# 2_cyber60-mx-matrix.net
KiCad netlist of a schematic drawn in Altium Designer
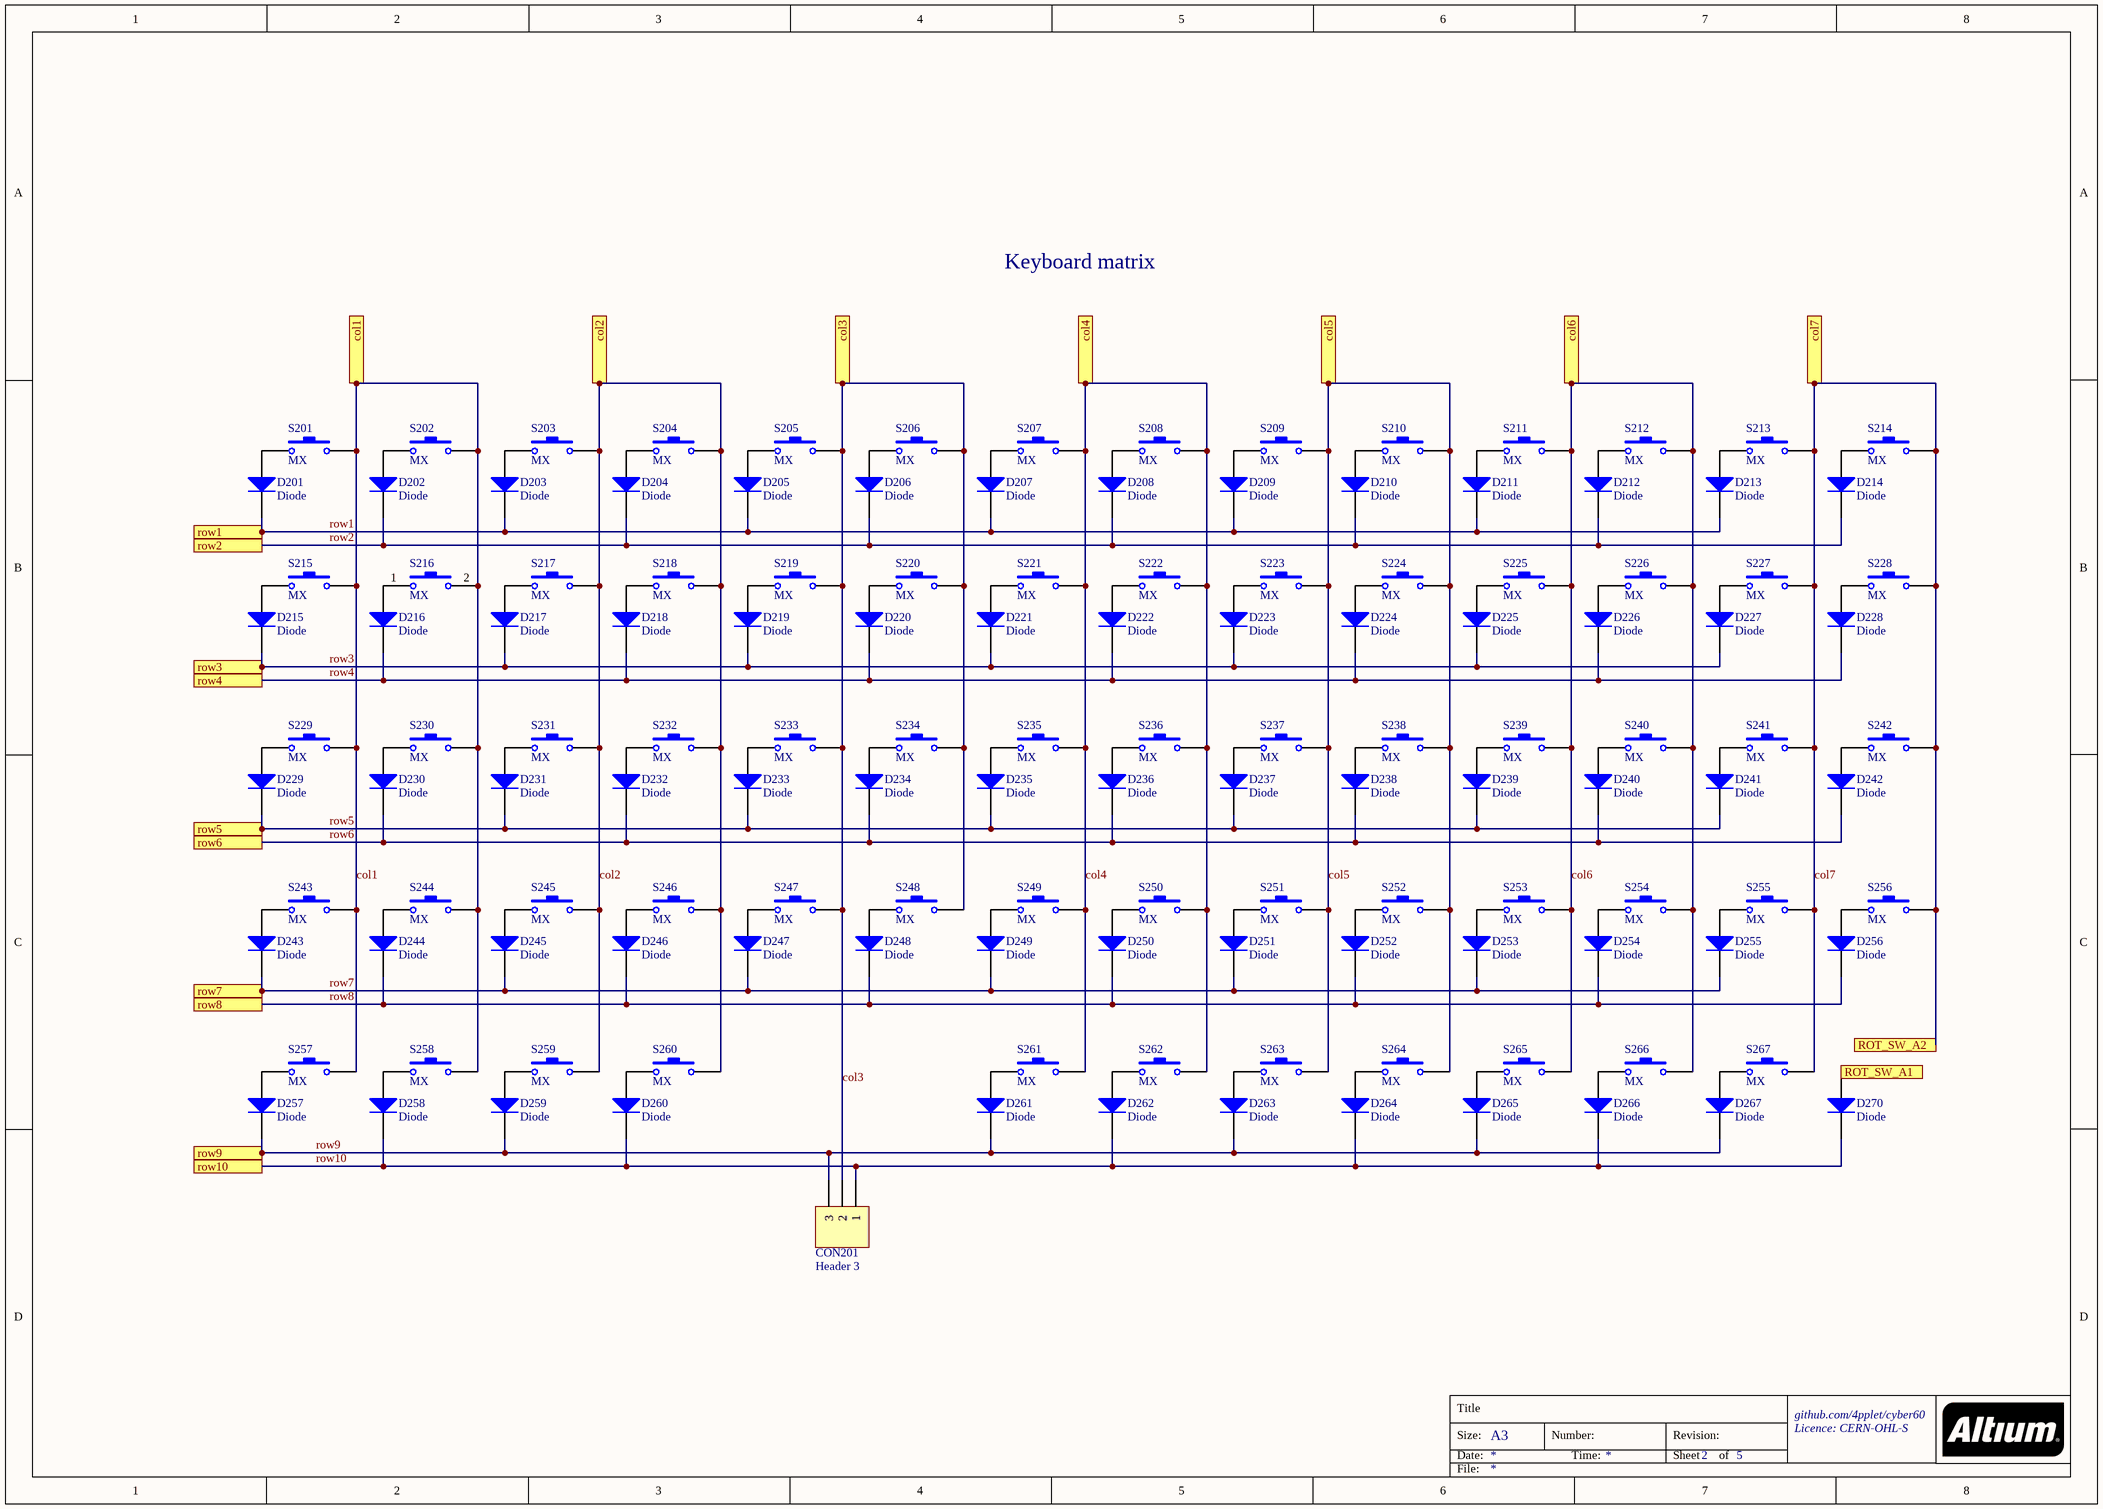
[diagram p0: 2_cyber60-mx-matrix.SchDoc]

(export (version "E")
  (design (tool "Eeschema 10.0.6"))
  (components
    (comp (ref "CON201")
      (value "Header 3")
      (footprint "HDR1X3")
      (description "Header, 3-Pin")
      (libsource (lib "Miscellaneous Connectors") (part "Header 3"))
    )
    (comp (ref "D201")
      (value "Diode")
      (footprint "SOD-123")
      (description "Default Diode")
      (fields (field (name "LCSC PART #") "C81598") (field (name "MRF.PART") "1N4148W"))
      (libsource (lib "Miscellaneous Devices") (part "Diode"))
    )
    (comp (ref "D202")
      (value "Diode")
      (footprint "SOD-123")
      (description "Default Diode")
      (fields (field (name "LCSC PART #") "C81598") (field (name "MRF.PART") "1N4148W"))
      (libsource (lib "Miscellaneous Devices") (part "Diode"))
    )
    (comp (ref "D203")
      (value "Diode")
      (footprint "SOD-123")
      (description "Default Diode")
      (fields (field (name "LCSC PART #") "C81598") (field (name "MRF.PART") "1N4148W"))
      (libsource (lib "Miscellaneous Devices") (part "Diode"))
    )
    (comp (ref "D204")
      (value "Diode")
      (footprint "SOD-123")
      (description "Default Diode")
      (fields (field (name "LCSC PART #") "C81598") (field (name "MRF.PART") "1N4148W"))
      (libsource (lib "Miscellaneous Devices") (part "Diode"))
    )
    (comp (ref "D205")
      (value "Diode")
      (footprint "SOD-123")
      (description "Default Diode")
      (fields (field (name "LCSC PART #") "C81598") (field (name "MRF.PART") "1N4148W"))
      (libsource (lib "Miscellaneous Devices") (part "Diode"))
    )
    (comp (ref "D206")
      (value "Diode")
      (footprint "SOD-123")
      (description "Default Diode")
      (fields (field (name "LCSC PART #") "C81598") (field (name "MRF.PART") "1N4148W"))
      (libsource (lib "Miscellaneous Devices") (part "Diode"))
    )
    (comp (ref "D207")
      (value "Diode")
      (footprint "SOD-123")
      (description "Default Diode")
      (fields (field (name "LCSC PART #") "C81598") (field (name "MRF.PART") "1N4148W"))
      (libsource (lib "Miscellaneous Devices") (part "Diode"))
    )
    (comp (ref "D208")
      (value "Diode")
      (footprint "SOD-123")
      (description "Default Diode")
      (fields (field (name "LCSC PART #") "C81598") (field (name "MRF.PART") "1N4148W"))
      (libsource (lib "Miscellaneous Devices") (part "Diode"))
    )
    (comp (ref "D209")
      (value "Diode")
      (footprint "SOD-123")
      (description "Default Diode")
      (fields (field (name "LCSC PART #") "C81598") (field (name "MRF.PART") "1N4148W"))
      (libsource (lib "Miscellaneous Devices") (part "Diode"))
    )
    (comp (ref "D210")
      (value "Diode")
      (footprint "SOD-123")
      (description "Default Diode")
      (fields (field (name "LCSC PART #") "C81598") (field (name "MRF.PART") "1N4148W"))
      (libsource (lib "Miscellaneous Devices") (part "Diode"))
    )
    (comp (ref "D211")
      (value "Diode")
      (footprint "SOD-123")
      (description "Default Diode")
      (fields (field (name "LCSC PART #") "C81598") (field (name "MRF.PART") "1N4148W"))
      (libsource (lib "Miscellaneous Devices") (part "Diode"))
    )
    (comp (ref "D212")
      (value "Diode")
      (footprint "SOD-123")
      (description "Default Diode")
      (fields (field (name "LCSC PART #") "C81598") (field (name "MRF.PART") "1N4148W"))
      (libsource (lib "Miscellaneous Devices") (part "Diode"))
    )
    (comp (ref "D213")
      (value "Diode")
      (footprint "SOD-123")
      (description "Default Diode")
      (fields (field (name "LCSC PART #") "C81598") (field (name "MRF.PART") "1N4148W"))
      (libsource (lib "Miscellaneous Devices") (part "Diode"))
    )
    (comp (ref "D214")
      (value "Diode")
      (footprint "SOD-123")
      (description "Default Diode")
      (fields (field (name "LCSC PART #") "C81598") (field (name "MRF.PART") "1N4148W"))
      (libsource (lib "Miscellaneous Devices") (part "Diode"))
    )
    (comp (ref "D215")
      (value "Diode")
      (footprint "SOD-123")
      (description "Default Diode")
      (fields (field (name "LCSC PART #") "C81598") (field (name "MRF.PART") "1N4148W"))
      (libsource (lib "Miscellaneous Devices") (part "Diode"))
    )
    (comp (ref "D216")
      (value "Diode")
      (footprint "SOD-123")
      (description "Default Diode")
      (fields (field (name "LCSC PART #") "C81598") (field (name "MRF.PART") "1N4148W"))
      (libsource (lib "Miscellaneous Devices") (part "Diode"))
    )
    (comp (ref "D217")
      (value "Diode")
      (footprint "SOD-123")
      (description "Default Diode")
      (fields (field (name "LCSC PART #") "C81598") (field (name "MRF.PART") "1N4148W"))
      (libsource (lib "Miscellaneous Devices") (part "Diode"))
    )
    (comp (ref "D218")
      (value "Diode")
      (footprint "SOD-123")
      (description "Default Diode")
      (fields (field (name "LCSC PART #") "C81598") (field (name "MRF.PART") "1N4148W"))
      (libsource (lib "Miscellaneous Devices") (part "Diode"))
    )
    (comp (ref "D219")
      (value "Diode")
      (footprint "SOD-123")
      (description "Default Diode")
      (fields (field (name "LCSC PART #") "C81598") (field (name "MRF.PART") "1N4148W"))
      (libsource (lib "Miscellaneous Devices") (part "Diode"))
    )
    (comp (ref "D220")
      (value "Diode")
      (footprint "SOD-123")
      (description "Default Diode")
      (fields (field (name "LCSC PART #") "C81598") (field (name "MRF.PART") "1N4148W"))
      (libsource (lib "Miscellaneous Devices") (part "Diode"))
    )
    (comp (ref "D221")
      (value "Diode")
      (footprint "SOD-123")
      (description "Default Diode")
      (fields (field (name "LCSC PART #") "C81598") (field (name "MRF.PART") "1N4148W"))
      (libsource (lib "Miscellaneous Devices") (part "Diode"))
    )
    (comp (ref "D222")
      (value "Diode")
      (footprint "SOD-123")
      (description "Default Diode")
      (fields (field (name "LCSC PART #") "C81598") (field (name "MRF.PART") "1N4148W"))
      (libsource (lib "Miscellaneous Devices") (part "Diode"))
    )
    (comp (ref "D223")
      (value "Diode")
      (footprint "SOD-123")
      (description "Default Diode")
      (fields (field (name "LCSC PART #") "C81598") (field (name "MRF.PART") "1N4148W"))
      (libsource (lib "Miscellaneous Devices") (part "Diode"))
    )
    (comp (ref "D224")
      (value "Diode")
      (footprint "SOD-123")
      (description "Default Diode")
      (fields (field (name "LCSC PART #") "C81598") (field (name "MRF.PART") "1N4148W"))
      (libsource (lib "Miscellaneous Devices") (part "Diode"))
    )
    (comp (ref "D225")
      (value "Diode")
      (footprint "SOD-123")
      (description "Default Diode")
      (fields (field (name "LCSC PART #") "C81598") (field (name "MRF.PART") "1N4148W"))
      (libsource (lib "Miscellaneous Devices") (part "Diode"))
    )
    (comp (ref "D226")
      (value "Diode")
      (footprint "SOD-123")
      (description "Default Diode")
      (fields (field (name "LCSC PART #") "C81598") (field (name "MRF.PART") "1N4148W"))
      (libsource (lib "Miscellaneous Devices") (part "Diode"))
    )
    (comp (ref "D227")
      (value "Diode")
      (footprint "SOD-123")
      (description "Default Diode")
      (fields (field (name "LCSC PART #") "C81598") (field (name "MRF.PART") "1N4148W"))
      (libsource (lib "Miscellaneous Devices") (part "Diode"))
    )
    (comp (ref "D228")
      (value "Diode")
      (footprint "SOD-123")
      (description "Default Diode")
      (fields (field (name "LCSC PART #") "C81598") (field (name "MRF.PART") "1N4148W"))
      (libsource (lib "Miscellaneous Devices") (part "Diode"))
    )
    (comp (ref "D229")
      (value "Diode")
      (footprint "SOD-123")
      (description "Default Diode")
      (fields (field (name "LCSC PART #") "C81598") (field (name "MRF.PART") "1N4148W"))
      (libsource (lib "Miscellaneous Devices") (part "Diode"))
    )
    (comp (ref "D230")
      (value "Diode")
      (footprint "SOD-123")
      (description "Default Diode")
      (fields (field (name "LCSC PART #") "C81598") (field (name "MRF.PART") "1N4148W"))
      (libsource (lib "Miscellaneous Devices") (part "Diode"))
    )
    (comp (ref "D231")
      (value "Diode")
      (footprint "SOD-123")
      (description "Default Diode")
      (fields (field (name "LCSC PART #") "C81598") (field (name "MRF.PART") "1N4148W"))
      (libsource (lib "Miscellaneous Devices") (part "Diode"))
    )
    (comp (ref "D232")
      (value "Diode")
      (footprint "SOD-123")
      (description "Default Diode")
      (fields (field (name "LCSC PART #") "C81598") (field (name "MRF.PART") "1N4148W"))
      (libsource (lib "Miscellaneous Devices") (part "Diode"))
    )
    (comp (ref "D233")
      (value "Diode")
      (footprint "SOD-123")
      (description "Default Diode")
      (fields (field (name "LCSC PART #") "C81598") (field (name "MRF.PART") "1N4148W"))
      (libsource (lib "Miscellaneous Devices") (part "Diode"))
    )
    (comp (ref "D234")
      (value "Diode")
      (footprint "SOD-123")
      (description "Default Diode")
      (fields (field (name "LCSC PART #") "C81598") (field (name "MRF.PART") "1N4148W"))
      (libsource (lib "Miscellaneous Devices") (part "Diode"))
    )
    (comp (ref "D235")
      (value "Diode")
      (footprint "SOD-123")
      (description "Default Diode")
      (fields (field (name "LCSC PART #") "C81598") (field (name "MRF.PART") "1N4148W"))
      (libsource (lib "Miscellaneous Devices") (part "Diode"))
    )
    (comp (ref "D236")
      (value "Diode")
      (footprint "SOD-123")
      (description "Default Diode")
      (fields (field (name "LCSC PART #") "C81598") (field (name "MRF.PART") "1N4148W"))
      (libsource (lib "Miscellaneous Devices") (part "Diode"))
    )
    (comp (ref "D237")
      (value "Diode")
      (footprint "SOD-123")
      (description "Default Diode")
      (fields (field (name "LCSC PART #") "C81598") (field (name "MRF.PART") "1N4148W"))
      (libsource (lib "Miscellaneous Devices") (part "Diode"))
    )
    (comp (ref "D238")
      (value "Diode")
      (footprint "SOD-123")
      (description "Default Diode")
      (fields (field (name "LCSC PART #") "C81598") (field (name "MRF.PART") "1N4148W"))
      (libsource (lib "Miscellaneous Devices") (part "Diode"))
    )
    (comp (ref "D239")
      (value "Diode")
      (footprint "SOD-123")
      (description "Default Diode")
      (fields (field (name "LCSC PART #") "C81598") (field (name "MRF.PART") "1N4148W"))
      (libsource (lib "Miscellaneous Devices") (part "Diode"))
    )
    (comp (ref "D240")
      (value "Diode")
      (footprint "SOD-123")
      (description "Default Diode")
      (fields (field (name "LCSC PART #") "C81598") (field (name "MRF.PART") "1N4148W"))
      (libsource (lib "Miscellaneous Devices") (part "Diode"))
    )
    (comp (ref "D241")
      (value "Diode")
      (footprint "SOD-123")
      (description "Default Diode")
      (fields (field (name "LCSC PART #") "C81598") (field (name "MRF.PART") "1N4148W"))
      (libsource (lib "Miscellaneous Devices") (part "Diode"))
    )
    (comp (ref "D242")
      (value "Diode")
      (footprint "SOD-123")
      (description "Default Diode")
      (fields (field (name "LCSC PART #") "C81598") (field (name "MRF.PART") "1N4148W"))
      (libsource (lib "Miscellaneous Devices") (part "Diode"))
    )
    (comp (ref "D243")
      (value "Diode")
      (footprint "SOD-123")
      (description "Default Diode")
      (fields (field (name "LCSC PART #") "C81598") (field (name "MRF.PART") "1N4148W"))
      (libsource (lib "Miscellaneous Devices") (part "Diode"))
    )
    (comp (ref "D244")
      (value "Diode")
      (footprint "SOD-123")
      (description "Default Diode")
      (fields (field (name "LCSC PART #") "C81598") (field (name "MRF.PART") "1N4148W"))
      (libsource (lib "Miscellaneous Devices") (part "Diode"))
    )
    (comp (ref "D245")
      (value "Diode")
      (footprint "SOD-123")
      (description "Default Diode")
      (fields (field (name "LCSC PART #") "C81598") (field (name "MRF.PART") "1N4148W"))
      (libsource (lib "Miscellaneous Devices") (part "Diode"))
    )
    (comp (ref "D246")
      (value "Diode")
      (footprint "SOD-123")
      (description "Default Diode")
      (fields (field (name "LCSC PART #") "C81598") (field (name "MRF.PART") "1N4148W"))
      (libsource (lib "Miscellaneous Devices") (part "Diode"))
    )
    (comp (ref "D247")
      (value "Diode")
      (footprint "SOD-123")
      (description "Default Diode")
      (fields (field (name "LCSC PART #") "C81598") (field (name "MRF.PART") "1N4148W"))
      (libsource (lib "Miscellaneous Devices") (part "Diode"))
    )
    (comp (ref "D248")
      (value "Diode")
      (footprint "SOD-123")
      (description "Default Diode")
      (fields (field (name "LCSC PART #") "C81598") (field (name "MRF.PART") "1N4148W"))
      (libsource (lib "Miscellaneous Devices") (part "Diode"))
    )
    (comp (ref "D249")
      (value "Diode")
      (footprint "SOD-123")
      (description "Default Diode")
      (fields (field (name "LCSC PART #") "C81598") (field (name "MRF.PART") "1N4148W"))
      (libsource (lib "Miscellaneous Devices") (part "Diode"))
    )
    (comp (ref "D250")
      (value "Diode")
      (footprint "SOD-123")
      (description "Default Diode")
      (fields (field (name "LCSC PART #") "C81598") (field (name "MRF.PART") "1N4148W"))
      (libsource (lib "Miscellaneous Devices") (part "Diode"))
    )
    (comp (ref "D251")
      (value "Diode")
      (footprint "SOD-123")
      (description "Default Diode")
      (fields (field (name "LCSC PART #") "C81598") (field (name "MRF.PART") "1N4148W"))
      (libsource (lib "Miscellaneous Devices") (part "Diode"))
    )
    (comp (ref "D252")
      (value "Diode")
      (footprint "SOD-123")
      (description "Default Diode")
      (fields (field (name "LCSC PART #") "C81598") (field (name "MRF.PART") "1N4148W"))
      (libsource (lib "Miscellaneous Devices") (part "Diode"))
    )
    (comp (ref "D253")
      (value "Diode")
      (footprint "SOD-123")
      (description "Default Diode")
      (fields (field (name "LCSC PART #") "C81598") (field (name "MRF.PART") "1N4148W"))
      (libsource (lib "Miscellaneous Devices") (part "Diode"))
    )
    (comp (ref "D254")
      (value "Diode")
      (footprint "SOD-123")
      (description "Default Diode")
      (fields (field (name "LCSC PART #") "C81598") (field (name "MRF.PART") "1N4148W"))
      (libsource (lib "Miscellaneous Devices") (part "Diode"))
    )
    (comp (ref "D255")
      (value "Diode")
      (footprint "SOD-123")
      (description "Default Diode")
      (fields (field (name "LCSC PART #") "C81598") (field (name "MRF.PART") "1N4148W"))
      (libsource (lib "Miscellaneous Devices") (part "Diode"))
    )
    (comp (ref "D256")
      (value "Diode")
      (footprint "SOD-123")
      (description "Default Diode")
      (fields (field (name "LCSC PART #") "C81598") (field (name "MRF.PART") "1N4148W"))
      (libsource (lib "Miscellaneous Devices") (part "Diode"))
    )
    (comp (ref "D257")
      (value "Diode")
      (footprint "SOD-123")
      (description "Default Diode")
      (fields (field (name "LCSC PART #") "C81598") (field (name "MRF.PART") "1N4148W"))
      (libsource (lib "Miscellaneous Devices") (part "Diode"))
    )
    (comp (ref "D258")
      (value "Diode")
      (footprint "SOD-123")
      (description "Default Diode")
      (fields (field (name "LCSC PART #") "C81598") (field (name "MRF.PART") "1N4148W"))
      (libsource (lib "Miscellaneous Devices") (part "Diode"))
    )
    (comp (ref "D259")
      (value "Diode")
      (footprint "SOD-123")
      (description "Default Diode")
      (fields (field (name "LCSC PART #") "C81598") (field (name "MRF.PART") "1N4148W"))
      (libsource (lib "Miscellaneous Devices") (part "Diode"))
    )
    (comp (ref "D260")
      (value "Diode")
      (footprint "SOD-123")
      (description "Default Diode")
      (fields (field (name "LCSC PART #") "C81598") (field (name "MRF.PART") "1N4148W"))
      (libsource (lib "Miscellaneous Devices") (part "Diode"))
    )
    (comp (ref "D261")
      (value "Diode")
      (footprint "SOD-123")
      (description "Default Diode")
      (fields (field (name "LCSC PART #") "C81598") (field (name "MRF.PART") "1N4148W"))
      (libsource (lib "Miscellaneous Devices") (part "Diode"))
    )
    (comp (ref "D262")
      (value "Diode")
      (footprint "SOD-123")
      (description "Default Diode")
      (fields (field (name "LCSC PART #") "C81598") (field (name "MRF.PART") "1N4148W"))
      (libsource (lib "Miscellaneous Devices") (part "Diode"))
    )
    (comp (ref "D263")
      (value "Diode")
      (footprint "SOD-123")
      (description "Default Diode")
      (fields (field (name "LCSC PART #") "C81598") (field (name "MRF.PART") "1N4148W"))
      (libsource (lib "Miscellaneous Devices") (part "Diode"))
    )
    (comp (ref "D264")
      (value "Diode")
      (footprint "SOD-123")
      (description "Default Diode")
      (fields (field (name "LCSC PART #") "C81598") (field (name "MRF.PART") "1N4148W"))
      (libsource (lib "Miscellaneous Devices") (part "Diode"))
    )
    (comp (ref "D265")
      (value "Diode")
      (footprint "SOD-123")
      (description "Default Diode")
      (fields (field (name "LCSC PART #") "C81598") (field (name "MRF.PART") "1N4148W"))
      (libsource (lib "Miscellaneous Devices") (part "Diode"))
    )
    (comp (ref "D266")
      (value "Diode")
      (footprint "SOD-123")
      (description "Default Diode")
      (fields (field (name "LCSC PART #") "C81598") (field (name "MRF.PART") "1N4148W"))
      (libsource (lib "Miscellaneous Devices") (part "Diode"))
    )
    (comp (ref "D267")
      (value "Diode")
      (footprint "SOD-123")
      (description "Default Diode")
      (fields (field (name "LCSC PART #") "C81598") (field (name "MRF.PART") "1N4148W"))
      (libsource (lib "Miscellaneous Devices") (part "Diode"))
    )
    (comp (ref "D270")
      (value "Diode")
      (footprint "SOD-123")
      (description "Default Diode")
      (fields (field (name "LCSC PART #") "C81598") (field (name "MRF.PART") "1N4148W"))
      (libsource (lib "Miscellaneous Devices") (part "Diode"))
    )
    (comp (ref "S201")
      (value "MX")
      (footprint "MX-switch - switched pol")
      (description "Switch")
      (libsource (lib "Miscellaneous Devices") (part "SW-PB"))
    )
    (comp (ref "S202")
      (value "MX")
      (footprint "MX-switch - switched pol - connector")
      (description "Switch")
      (libsource (lib "Miscellaneous Devices") (part "SW-PB"))
    )
    (comp (ref "S203")
      (value "MX")
      (footprint "MX-switch - switched pol")
      (description "Switch")
      (libsource (lib "Miscellaneous Devices") (part "SW-PB"))
    )
    (comp (ref "S204")
      (value "MX")
      (footprint "MX-switch")
      (description "Switch")
      (libsource (lib "Miscellaneous Devices") (part "SW-PB"))
    )
    (comp (ref "S205")
      (value "MX")
      (footprint "MX-switch - switched pol")
      (description "Switch")
      (libsource (lib "Miscellaneous Devices") (part "SW-PB"))
    )
    (comp (ref "S206")
      (value "MX")
      (footprint "MX-switch - switched pol")
      (description "Switch")
      (libsource (lib "Miscellaneous Devices") (part "SW-PB"))
    )
    (comp (ref "S207")
      (value "MX")
      (footprint "MX-switch - switched pol")
      (description "Switch")
      (libsource (lib "Miscellaneous Devices") (part "SW-PB"))
    )
    (comp (ref "S208")
      (value "MX")
      (footprint "MX-switch - switched pol")
      (description "Switch")
      (libsource (lib "Miscellaneous Devices") (part "SW-PB"))
    )
    (comp (ref "S209")
      (value "MX")
      (footprint "MX-switch - switched pol")
      (description "Switch")
      (libsource (lib "Miscellaneous Devices") (part "SW-PB"))
    )
    (comp (ref "S210")
      (value "MX")
      (footprint "MX-switch - switched pol")
      (description "Switch")
      (libsource (lib "Miscellaneous Devices") (part "SW-PB"))
    )
    (comp (ref "S211")
      (value "MX")
      (footprint "MX-switch - switched pol")
      (description "Switch")
      (libsource (lib "Miscellaneous Devices") (part "SW-PB"))
    )
    (comp (ref "S212")
      (value "MX")
      (footprint "MX-switch - switched pol")
      (description "Switch")
      (libsource (lib "Miscellaneous Devices") (part "SW-PB"))
    )
    (comp (ref "S213")
      (value "MX")
      (footprint "MX-switch - switched pol")
      (description "Switch")
      (libsource (lib "Miscellaneous Devices") (part "SW-PB"))
    )
    (comp (ref "S214")
      (value "MX")
      (footprint "MX-switch - switched pol")
      (description "Switch")
      (libsource (lib "Miscellaneous Devices") (part "SW-PB"))
    )
    (comp (ref "S215")
      (value "MX")
      (footprint "MX-switch - 1.5U - switched pol")
      (description "TAB")
      (libsource (lib "Miscellaneous Devices") (part "SW-PB"))
    )
    (comp (ref "S216")
      (value "MX")
      (footprint "MX-switch - switched pol")
      (description "Switch")
      (libsource (lib "") (part "SW-PB_1"))
    )
    (comp (ref "S217")
      (value "MX")
      (footprint "MX-switch - switched pol")
      (description "Switch")
      (libsource (lib "Miscellaneous Devices") (part "SW-PB"))
    )
    (comp (ref "S218")
      (value "MX")
      (footprint "MX-switch - switched pol")
      (description "Switch")
      (libsource (lib "Miscellaneous Devices") (part "SW-PB"))
    )
    (comp (ref "S219")
      (value "MX")
      (footprint "MX-switch - switched pol")
      (description "Switch")
      (libsource (lib "Miscellaneous Devices") (part "SW-PB"))
    )
    (comp (ref "S220")
      (value "MX")
      (footprint "MX-switch")
      (description "Switch")
      (libsource (lib "Miscellaneous Devices") (part "SW-PB"))
    )
    (comp (ref "S221")
      (value "MX")
      (footprint "MX-switch - switched pol")
      (description "Switch")
      (libsource (lib "Miscellaneous Devices") (part "SW-PB"))
    )
    (comp (ref "S222")
      (value "MX")
      (footprint "MX-switch - switched pol")
      (description "Switch")
      (libsource (lib "Miscellaneous Devices") (part "SW-PB"))
    )
    (comp (ref "S223")
      (value "MX")
      (footprint "MX-switch - switched pol")
      (description "Switch")
      (libsource (lib "Miscellaneous Devices") (part "SW-PB"))
    )
    (comp (ref "S224")
      (value "MX")
      (footprint "MX-switch - switched pol")
      (description "Switch")
      (libsource (lib "Miscellaneous Devices") (part "SW-PB"))
    )
    (comp (ref "S225")
      (value "MX")
      (footprint "MX-switch - switched pol")
      (description "Switch")
      (libsource (lib "Miscellaneous Devices") (part "SW-PB"))
    )
    (comp (ref "S226")
      (value "MX")
      (footprint "MX-switch")
      (description "Switch")
      (libsource (lib "Miscellaneous Devices") (part "SW-PB"))
    )
    (comp (ref "S227")
      (value "MX")
      (footprint "MX-switch")
      (description "Switch")
      (libsource (lib "Miscellaneous Devices") (part "SW-PB"))
    )
    (comp (ref "S228")
      (value "MX")
      (footprint "MX-switch - backspace")
      (description "Switch")
      (libsource (lib "Miscellaneous Devices") (part "SW-PB"))
    )
    (comp (ref "S229")
      (value "MX")
      (footprint "MX-switch - CAPS")
      (description "Switch")
      (libsource (lib "Miscellaneous Devices") (part "SW-PB"))
    )
    (comp (ref "S230")
      (value "MX")
      (footprint "MX-switch - switched pol")
      (description "Switch")
      (libsource (lib "Miscellaneous Devices") (part "SW-PB"))
    )
    (comp (ref "S231")
      (value "MX")
      (footprint "MX-switch - switched pol")
      (description "Switch")
      (libsource (lib "Miscellaneous Devices") (part "SW-PB"))
    )
    (comp (ref "S232")
      (value "MX")
      (footprint "MX-switch - switched pol")
      (description "Switch")
      (libsource (lib "Miscellaneous Devices") (part "SW-PB"))
    )
    (comp (ref "S233")
      (value "MX")
      (footprint "MX-switch - switched pol")
      (description "Switch")
      (libsource (lib "Miscellaneous Devices") (part "SW-PB"))
    )
    (comp (ref "S234")
      (value "MX")
      (footprint "MX-switch")
      (description "Switch")
      (libsource (lib "Miscellaneous Devices") (part "SW-PB"))
    )
    (comp (ref "S235")
      (value "MX")
      (footprint "MX-switch - switched pol")
      (description "Switch")
      (libsource (lib "Miscellaneous Devices") (part "SW-PB"))
    )
    (comp (ref "S236")
      (value "MX")
      (footprint "MX-switch - switched pol")
      (description "Switch")
      (libsource (lib "Miscellaneous Devices") (part "SW-PB"))
    )
    (comp (ref "S237")
      (value "MX")
      (footprint "MX-switch - switched pol")
      (description "Switch")
      (libsource (lib "Miscellaneous Devices") (part "SW-PB"))
    )
    (comp (ref "S238")
      (value "MX")
      (footprint "MX-switch - switched pol")
      (description "Switch")
      (libsource (lib "Miscellaneous Devices") (part "SW-PB"))
    )
    (comp (ref "S239")
      (value "MX")
      (footprint "MX-switch")
      (description "Switch")
      (libsource (lib "Miscellaneous Devices") (part "SW-PB"))
    )
    (comp (ref "S240")
      (value "MX")
      (footprint "MX-switch - switched pol")
      (description "Switch")
      (libsource (lib "Miscellaneous Devices") (part "SW-PB"))
    )
    (comp (ref "S241")
      (value "MX")
      (footprint "MX-switch")
      (description "Switch")
      (libsource (lib "Miscellaneous Devices") (part "SW-PB"))
    )
    (comp (ref "S242")
      (value "MX")
      (footprint "MX-switch - 1.5U")
      (description "Switch")
      (libsource (lib "Miscellaneous Devices") (part "SW-PB"))
    )
    (comp (ref "S243")
      (value "MX")
      (footprint "MX-switch - Left shift")
      (description "Switch")
      (libsource (lib "Miscellaneous Devices") (part "SW-PB"))
    )
    (comp (ref "S244")
      (value "MX")
      (footprint "MX-switch - switched pol")
      (description "Switch")
      (libsource (lib "Miscellaneous Devices") (part "SW-PB"))
    )
    (comp (ref "S245")
      (value "MX")
      (footprint "MX-switch - switched pol")
      (description "Switch")
      (libsource (lib "Miscellaneous Devices") (part "SW-PB"))
    )
    (comp (ref "S246")
      (value "MX")
      (footprint "MX-switch - switched pol")
      (description "Switch")
      (libsource (lib "Miscellaneous Devices") (part "SW-PB"))
    )
    (comp (ref "S247")
      (value "MX")
      (footprint "MX-switch - switched pol")
      (description "Switch")
      (libsource (lib "Miscellaneous Devices") (part "SW-PB"))
    )
    (comp (ref "S248")
      (value "MX")
      (footprint "MX-switch")
      (description "Switch")
      (libsource (lib "Miscellaneous Devices") (part "SW-PB"))
    )
    (comp (ref "S249")
      (value "MX")
      (footprint "MX-switch - switched pol")
      (description "Switch")
      (libsource (lib "Miscellaneous Devices") (part "SW-PB"))
    )
    (comp (ref "S250")
      (value "MX")
      (footprint "MX-switch - switched pol")
      (description "Switch")
      (libsource (lib "Miscellaneous Devices") (part "SW-PB"))
    )
    (comp (ref "S251")
      (value "MX")
      (footprint "MX-switch - switched pol")
      (description "Switch")
      (libsource (lib "Miscellaneous Devices") (part "SW-PB"))
    )
    (comp (ref "S252")
      (value "MX")
      (footprint "MX-switch - switched pol")
      (description "Switch")
      (libsource (lib "Miscellaneous Devices") (part "SW-PB"))
    )
    (comp (ref "S253")
      (value "MX")
      (footprint "MX-switch - switched pol")
      (description "Switch")
      (libsource (lib "Miscellaneous Devices") (part "SW-PB"))
    )
    (comp (ref "S254")
      (value "MX")
      (footprint "MX-switch - switched pol")
      (description "Switch")
      (libsource (lib "Miscellaneous Devices") (part "SW-PB"))
    )
    (comp (ref "S255")
      (value "MX")
      (footprint "MX-switch")
      (description "Switch")
      (libsource (lib "Miscellaneous Devices") (part "SW-PB"))
    )
    (comp (ref "S256")
      (value "MX")
      (footprint "MX-switch - Enter")
      (description "Switch")
      (libsource (lib "Miscellaneous Devices") (part "SW-PB"))
    )
    (comp (ref "S257")
      (value "MX")
      (footprint "MX-switch - 1.5u MOD-L")
      (description "Switch")
      (libsource (lib "Miscellaneous Devices") (part "SW-PB"))
    )
    (comp (ref "S258")
      (value "MX")
      (footprint "MX-switch - 1u MOD-L")
      (description "Switch")
      (libsource (lib "Miscellaneous Devices") (part "SW-PB"))
    )
    (comp (ref "S259")
      (value "MX")
      (footprint "MX-switch - 1.5u MOD-L")
      (description "Switch")
      (libsource (lib "Miscellaneous Devices") (part "SW-PB"))
    )
    (comp (ref "S260")
      (value "MX")
      (footprint "MX-switch - L split space_V2")
      (description "Switch")
      (libsource (lib "Miscellaneous Devices") (part "SW-PB"))
    )
    (comp (ref "S261")
      (value "MX")
      (footprint "MX-switch - Space_V3")
      (description "Switch")
      (libsource (lib "Miscellaneous Devices") (part "SW-PB"))
    )
    (comp (ref "S262")
      (value "MX")
      (footprint "MX-switch - R split space_V2")
      (description "Switch")
      (libsource (lib "Miscellaneous Devices") (part "SW-PB"))
    )
    (comp (ref "S263")
      (value "MX")
      (footprint "MX-switch - switched pol")
      (description "Switch")
      (libsource (lib "Miscellaneous Devices") (part "SW-PB"))
    )
    (comp (ref "S264")
      (value "MX")
      (footprint "MX-switch - 1.5u MOD-R")
      (description "Switch")
      (libsource (lib "Miscellaneous Devices") (part "SW-PB"))
    )
    (comp (ref "S265")
      (value "MX")
      (footprint "MX-switch - 1u MOD-R")
      (description "Switch")
      (libsource (lib "Miscellaneous Devices") (part "SW-PB"))
    )
    (comp (ref "S266")
      (value "MX")
      (footprint "MX-switch - 1.5u MOD-R")
      (description "Switch")
      (libsource (lib "Miscellaneous Devices") (part "SW-PB"))
    )
    (comp (ref "S267")
      (value "MX")
      (footprint "MX-switch - right shift")
      (description "Switch")
      (libsource (lib "Miscellaneous Devices") (part "SW-PB"))
    )
  )
  (nets
    (net (code "1") (name "/ROT_SW_A1") (class "Default")
      (node (ref "D270") (pin "1") (pinfunction "A_1") (pintype "passive"))
    )
    (net (code "2") (name "/col1") (class "Default")
      (node (ref "S201") (pin "2") (pinfunction "2_2") (pintype "passive"))
      (node (ref "S202") (pin "2") (pinfunction "2_2") (pintype "passive"))
      (node (ref "S215") (pin "2") (pinfunction "2_2") (pintype "passive"))
      (node (ref "S216") (pin "2") (pinfunction "2_2") (pintype "passive"))
      (node (ref "S229") (pin "2") (pinfunction "2_2") (pintype "passive"))
      (node (ref "S230") (pin "2") (pinfunction "2_2") (pintype "passive"))
      (node (ref "S243") (pin "2") (pinfunction "2_2") (pintype "passive"))
      (node (ref "S244") (pin "2") (pinfunction "2_2") (pintype "passive"))
      (node (ref "S257") (pin "2") (pinfunction "2_2") (pintype "passive"))
      (node (ref "S258") (pin "2") (pinfunction "2_2") (pintype "passive"))
    )
    (net (code "3") (name "/col2") (class "Default")
      (node (ref "S203") (pin "2") (pinfunction "2_2") (pintype "passive"))
      (node (ref "S204") (pin "2") (pinfunction "2_2") (pintype "passive"))
      (node (ref "S217") (pin "2") (pinfunction "2_2") (pintype "passive"))
      (node (ref "S218") (pin "2") (pinfunction "2_2") (pintype "passive"))
      (node (ref "S231") (pin "2") (pinfunction "2_2") (pintype "passive"))
      (node (ref "S232") (pin "2") (pinfunction "2_2") (pintype "passive"))
      (node (ref "S245") (pin "2") (pinfunction "2_2") (pintype "passive"))
      (node (ref "S246") (pin "2") (pinfunction "2_2") (pintype "passive"))
      (node (ref "S259") (pin "2") (pinfunction "2_2") (pintype "passive"))
      (node (ref "S260") (pin "2") (pinfunction "2_2") (pintype "passive"))
    )
    (net (code "4") (name "/col3") (class "Default")
      (node (ref "CON201") (pin "2") (pinfunction "2_2") (pintype "passive"))
      (node (ref "S205") (pin "2") (pinfunction "2_2") (pintype "passive"))
      (node (ref "S206") (pin "2") (pinfunction "2_2") (pintype "passive"))
      (node (ref "S219") (pin "2") (pinfunction "2_2") (pintype "passive"))
      (node (ref "S220") (pin "2") (pinfunction "2_2") (pintype "passive"))
      (node (ref "S233") (pin "2") (pinfunction "2_2") (pintype "passive"))
      (node (ref "S234") (pin "2") (pinfunction "2_2") (pintype "passive"))
      (node (ref "S247") (pin "2") (pinfunction "2_2") (pintype "passive"))
      (node (ref "S248") (pin "2") (pinfunction "2_2") (pintype "passive"))
    )
    (net (code "5") (name "/col4") (class "Default")
      (node (ref "S207") (pin "2") (pinfunction "2_2") (pintype "passive"))
      (node (ref "S208") (pin "2") (pinfunction "2_2") (pintype "passive"))
      (node (ref "S221") (pin "2") (pinfunction "2_2") (pintype "passive"))
      (node (ref "S222") (pin "2") (pinfunction "2_2") (pintype "passive"))
      (node (ref "S235") (pin "2") (pinfunction "2_2") (pintype "passive"))
      (node (ref "S236") (pin "2") (pinfunction "2_2") (pintype "passive"))
      (node (ref "S249") (pin "2") (pinfunction "2_2") (pintype "passive"))
      (node (ref "S250") (pin "2") (pinfunction "2_2") (pintype "passive"))
      (node (ref "S261") (pin "1") (pinfunction "1_1") (pintype "passive"))
      (node (ref "S262") (pin "2") (pinfunction "2_2") (pintype "passive"))
    )
    (net (code "6") (name "/col5") (class "Default")
      (node (ref "S209") (pin "2") (pinfunction "2_2") (pintype "passive"))
      (node (ref "S210") (pin "2") (pinfunction "2_2") (pintype "passive"))
      (node (ref "S223") (pin "2") (pinfunction "2_2") (pintype "passive"))
      (node (ref "S224") (pin "2") (pinfunction "2_2") (pintype "passive"))
      (node (ref "S237") (pin "2") (pinfunction "2_2") (pintype "passive"))
      (node (ref "S238") (pin "2") (pinfunction "2_2") (pintype "passive"))
      (node (ref "S251") (pin "2") (pinfunction "2_2") (pintype "passive"))
      (node (ref "S252") (pin "2") (pinfunction "2_2") (pintype "passive"))
      (node (ref "S263") (pin "2") (pinfunction "2_2") (pintype "passive"))
      (node (ref "S264") (pin "1") (pinfunction "1_1") (pintype "passive"))
    )
    (net (code "7") (name "/col6") (class "Default")
      (node (ref "S211") (pin "2") (pinfunction "2_2") (pintype "passive"))
      (node (ref "S212") (pin "2") (pinfunction "2_2") (pintype "passive"))
      (node (ref "S225") (pin "2") (pinfunction "2_2") (pintype "passive"))
      (node (ref "S226") (pin "2") (pinfunction "2_2") (pintype "passive"))
      (node (ref "S239") (pin "2") (pinfunction "2_2") (pintype "passive"))
      (node (ref "S240") (pin "2") (pinfunction "2_2") (pintype "passive"))
      (node (ref "S253") (pin "2") (pinfunction "2_2") (pintype "passive"))
      (node (ref "S254") (pin "2") (pinfunction "2_2") (pintype "passive"))
      (node (ref "S265") (pin "2") (pinfunction "2_2") (pintype "passive"))
      (node (ref "S266") (pin "2") (pinfunction "2_2") (pintype "passive"))
    )
    (net (code "8") (name "/col7") (class "Default")
      (node (ref "S213") (pin "2") (pinfunction "2_2") (pintype "passive"))
      (node (ref "S214") (pin "2") (pinfunction "2_2") (pintype "passive"))
      (node (ref "S227") (pin "2") (pinfunction "2_2") (pintype "passive"))
      (node (ref "S228") (pin "1") (pinfunction "1_1") (pintype "passive"))
      (node (ref "S241") (pin "2") (pinfunction "2_2") (pintype "passive"))
      (node (ref "S242") (pin "2") (pinfunction "2_2") (pintype "passive"))
      (node (ref "S255") (pin "2") (pinfunction "2_2") (pintype "passive"))
      (node (ref "S256") (pin "2") (pinfunction "2_2") (pintype "passive"))
      (node (ref "S267") (pin "2") (pinfunction "2_2") (pintype "passive"))
    )
    (net (code "9") (name "/row1") (class "Default")
      (node (ref "D201") (pin "2") (pinfunction "K_2") (pintype "passive"))
      (node (ref "D203") (pin "2") (pinfunction "K_2") (pintype "passive"))
      (node (ref "D205") (pin "2") (pinfunction "K_2") (pintype "passive"))
      (node (ref "D207") (pin "2") (pinfunction "K_2") (pintype "passive"))
      (node (ref "D209") (pin "2") (pinfunction "K_2") (pintype "passive"))
      (node (ref "D211") (pin "2") (pinfunction "K_2") (pintype "passive"))
      (node (ref "D213") (pin "2") (pinfunction "K_2") (pintype "passive"))
    )
    (net (code "10") (name "/row2") (class "Default")
      (node (ref "D202") (pin "2") (pinfunction "K_2") (pintype "passive"))
      (node (ref "D204") (pin "2") (pinfunction "K_2") (pintype "passive"))
      (node (ref "D206") (pin "2") (pinfunction "K_2") (pintype "passive"))
      (node (ref "D208") (pin "2") (pinfunction "K_2") (pintype "passive"))
      (node (ref "D210") (pin "2") (pinfunction "K_2") (pintype "passive"))
      (node (ref "D212") (pin "2") (pinfunction "K_2") (pintype "passive"))
      (node (ref "D214") (pin "2") (pinfunction "K_2") (pintype "passive"))
    )
    (net (code "11") (name "/row3") (class "Default")
      (node (ref "D215") (pin "2") (pinfunction "K_2") (pintype "passive"))
      (node (ref "D217") (pin "2") (pinfunction "K_2") (pintype "passive"))
      (node (ref "D219") (pin "2") (pinfunction "K_2") (pintype "passive"))
      (node (ref "D221") (pin "2") (pinfunction "K_2") (pintype "passive"))
      (node (ref "D223") (pin "2") (pinfunction "K_2") (pintype "passive"))
      (node (ref "D225") (pin "2") (pinfunction "K_2") (pintype "passive"))
      (node (ref "D227") (pin "2") (pinfunction "K_2") (pintype "passive"))
    )
    (net (code "12") (name "/row4") (class "Default")
      (node (ref "D216") (pin "2") (pinfunction "K_2") (pintype "passive"))
      (node (ref "D218") (pin "2") (pinfunction "K_2") (pintype "passive"))
      (node (ref "D220") (pin "2") (pinfunction "K_2") (pintype "passive"))
      (node (ref "D222") (pin "2") (pinfunction "K_2") (pintype "passive"))
      (node (ref "D224") (pin "2") (pinfunction "K_2") (pintype "passive"))
      (node (ref "D226") (pin "2") (pinfunction "K_2") (pintype "passive"))
      (node (ref "D228") (pin "2") (pinfunction "K_2") (pintype "passive"))
    )
    (net (code "13") (name "/row5") (class "Default")
      (node (ref "D229") (pin "2") (pinfunction "K_2") (pintype "passive"))
      (node (ref "D231") (pin "2") (pinfunction "K_2") (pintype "passive"))
      (node (ref "D233") (pin "2") (pinfunction "K_2") (pintype "passive"))
      (node (ref "D235") (pin "2") (pinfunction "K_2") (pintype "passive"))
      (node (ref "D237") (pin "2") (pinfunction "K_2") (pintype "passive"))
      (node (ref "D239") (pin "2") (pinfunction "K_2") (pintype "passive"))
      (node (ref "D241") (pin "2") (pinfunction "K_2") (pintype "passive"))
    )
    (net (code "14") (name "/row6") (class "Default")
      (node (ref "D230") (pin "2") (pinfunction "K_2") (pintype "passive"))
      (node (ref "D232") (pin "2") (pinfunction "K_2") (pintype "passive"))
      (node (ref "D234") (pin "2") (pinfunction "K_2") (pintype "passive"))
      (node (ref "D236") (pin "2") (pinfunction "K_2") (pintype "passive"))
      (node (ref "D238") (pin "2") (pinfunction "K_2") (pintype "passive"))
      (node (ref "D240") (pin "2") (pinfunction "K_2") (pintype "passive"))
      (node (ref "D242") (pin "2") (pinfunction "K_2") (pintype "passive"))
    )
    (net (code "15") (name "/row7") (class "Default")
      (node (ref "D243") (pin "2") (pinfunction "K_2") (pintype "passive"))
      (node (ref "D245") (pin "2") (pinfunction "K_2") (pintype "passive"))
      (node (ref "D247") (pin "2") (pinfunction "K_2") (pintype "passive"))
      (node (ref "D249") (pin "2") (pinfunction "K_2") (pintype "passive"))
      (node (ref "D251") (pin "2") (pinfunction "K_2") (pintype "passive"))
      (node (ref "D253") (pin "2") (pinfunction "K_2") (pintype "passive"))
      (node (ref "D255") (pin "2") (pinfunction "K_2") (pintype "passive"))
    )
    (net (code "16") (name "/row8") (class "Default")
      (node (ref "D244") (pin "2") (pinfunction "K_2") (pintype "passive"))
      (node (ref "D246") (pin "2") (pinfunction "K_2") (pintype "passive"))
      (node (ref "D248") (pin "2") (pinfunction "K_2") (pintype "passive"))
      (node (ref "D250") (pin "2") (pinfunction "K_2") (pintype "passive"))
      (node (ref "D252") (pin "2") (pinfunction "K_2") (pintype "passive"))
      (node (ref "D254") (pin "2") (pinfunction "K_2") (pintype "passive"))
      (node (ref "D256") (pin "2") (pinfunction "K_2") (pintype "passive"))
    )
    (net (code "17") (name "/row9") (class "Default")
      (node (ref "CON201") (pin "3") (pinfunction "3_3") (pintype "passive"))
      (node (ref "D257") (pin "2") (pinfunction "K_2") (pintype "passive"))
      (node (ref "D259") (pin "2") (pinfunction "K_2") (pintype "passive"))
      (node (ref "D261") (pin "2") (pinfunction "K_2") (pintype "passive"))
      (node (ref "D263") (pin "2") (pinfunction "K_2") (pintype "passive"))
      (node (ref "D265") (pin "2") (pinfunction "K_2") (pintype "passive"))
      (node (ref "D267") (pin "2") (pinfunction "K_2") (pintype "passive"))
    )
    (net (code "18") (name "/row10") (class "Default")
      (node (ref "CON201") (pin "1") (pinfunction "1_1") (pintype "passive"))
      (node (ref "D258") (pin "2") (pinfunction "K_2") (pintype "passive"))
      (node (ref "D260") (pin "2") (pinfunction "K_2") (pintype "passive"))
      (node (ref "D262") (pin "2") (pinfunction "K_2") (pintype "passive"))
      (node (ref "D264") (pin "2") (pinfunction "K_2") (pintype "passive"))
      (node (ref "D266") (pin "2") (pinfunction "K_2") (pintype "passive"))
      (node (ref "D270") (pin "2") (pinfunction "K_2") (pintype "passive"))
    )
    (net (code "19") (name "Net-(D201-A)") (class "Default")
      (node (ref "D201") (pin "1") (pinfunction "A_1") (pintype "passive"))
      (node (ref "S201") (pin "1") (pinfunction "1_1") (pintype "passive"))
    )
    (net (code "20") (name "Net-(D202-A)") (class "Default")
      (node (ref "D202") (pin "1") (pinfunction "A_1") (pintype "passive"))
      (node (ref "S202") (pin "1") (pinfunction "1_1") (pintype "passive"))
    )
    (net (code "21") (name "Net-(D203-A)") (class "Default")
      (node (ref "D203") (pin "1") (pinfunction "A_1") (pintype "passive"))
      (node (ref "S203") (pin "1") (pinfunction "1_1") (pintype "passive"))
    )
    (net (code "22") (name "Net-(D204-A)") (class "Default")
      (node (ref "D204") (pin "1") (pinfunction "A_1") (pintype "passive"))
      (node (ref "S204") (pin "1") (pinfunction "1_1") (pintype "passive"))
    )
    (net (code "23") (name "Net-(D205-A)") (class "Default")
      (node (ref "D205") (pin "1") (pinfunction "A_1") (pintype "passive"))
      (node (ref "S205") (pin "1") (pinfunction "1_1") (pintype "passive"))
    )
    (net (code "24") (name "Net-(D206-A)") (class "Default")
      (node (ref "D206") (pin "1") (pinfunction "A_1") (pintype "passive"))
      (node (ref "S206") (pin "1") (pinfunction "1_1") (pintype "passive"))
    )
    (net (code "25") (name "Net-(D207-A)") (class "Default")
      (node (ref "D207") (pin "1") (pinfunction "A_1") (pintype "passive"))
      (node (ref "S207") (pin "1") (pinfunction "1_1") (pintype "passive"))
    )
    (net (code "26") (name "Net-(D208-A)") (class "Default")
      (node (ref "D208") (pin "1") (pinfunction "A_1") (pintype "passive"))
      (node (ref "S208") (pin "1") (pinfunction "1_1") (pintype "passive"))
    )
    (net (code "27") (name "Net-(D209-A)") (class "Default")
      (node (ref "D209") (pin "1") (pinfunction "A_1") (pintype "passive"))
      (node (ref "S209") (pin "1") (pinfunction "1_1") (pintype "passive"))
    )
    (net (code "28") (name "Net-(D210-A)") (class "Default")
      (node (ref "D210") (pin "1") (pinfunction "A_1") (pintype "passive"))
      (node (ref "S210") (pin "1") (pinfunction "1_1") (pintype "passive"))
    )
    (net (code "29") (name "Net-(D211-A)") (class "Default")
      (node (ref "D211") (pin "1") (pinfunction "A_1") (pintype "passive"))
      (node (ref "S211") (pin "1") (pinfunction "1_1") (pintype "passive"))
    )
    (net (code "30") (name "Net-(D212-A)") (class "Default")
      (node (ref "D212") (pin "1") (pinfunction "A_1") (pintype "passive"))
      (node (ref "S212") (pin "1") (pinfunction "1_1") (pintype "passive"))
    )
    (net (code "31") (name "Net-(D213-A)") (class "Default")
      (node (ref "D213") (pin "1") (pinfunction "A_1") (pintype "passive"))
      (node (ref "S213") (pin "1") (pinfunction "1_1") (pintype "passive"))
    )
    (net (code "32") (name "Net-(D214-A)") (class "Default")
      (node (ref "D214") (pin "1") (pinfunction "A_1") (pintype "passive"))
      (node (ref "S214") (pin "1") (pinfunction "1_1") (pintype "passive"))
    )
    (net (code "33") (name "Net-(D215-A)") (class "Default")
      (node (ref "D215") (pin "1") (pinfunction "A_1") (pintype "passive"))
      (node (ref "S215") (pin "1") (pinfunction "1_1") (pintype "passive"))
    )
    (net (code "34") (name "Net-(D216-A)") (class "Default")
      (node (ref "D216") (pin "1") (pinfunction "A_1") (pintype "passive"))
      (node (ref "S216") (pin "1") (pinfunction "1_1") (pintype "passive"))
    )
    (net (code "35") (name "Net-(D217-A)") (class "Default")
      (node (ref "D217") (pin "1") (pinfunction "A_1") (pintype "passive"))
      (node (ref "S217") (pin "1") (pinfunction "1_1") (pintype "passive"))
    )
    (net (code "36") (name "Net-(D218-A)") (class "Default")
      (node (ref "D218") (pin "1") (pinfunction "A_1") (pintype "passive"))
      (node (ref "S218") (pin "1") (pinfunction "1_1") (pintype "passive"))
    )
    (net (code "37") (name "Net-(D219-A)") (class "Default")
      (node (ref "D219") (pin "1") (pinfunction "A_1") (pintype "passive"))
      (node (ref "S219") (pin "1") (pinfunction "1_1") (pintype "passive"))
    )
    (net (code "38") (name "Net-(D220-A)") (class "Default")
      (node (ref "D220") (pin "1") (pinfunction "A_1") (pintype "passive"))
      (node (ref "S220") (pin "1") (pinfunction "1_1") (pintype "passive"))
    )
    (net (code "39") (name "Net-(D221-A)") (class "Default")
      (node (ref "D221") (pin "1") (pinfunction "A_1") (pintype "passive"))
      (node (ref "S221") (pin "1") (pinfunction "1_1") (pintype "passive"))
    )
    (net (code "40") (name "Net-(D222-A)") (class "Default")
      (node (ref "D222") (pin "1") (pinfunction "A_1") (pintype "passive"))
      (node (ref "S222") (pin "1") (pinfunction "1_1") (pintype "passive"))
    )
    (net (code "41") (name "Net-(D223-A)") (class "Default")
      (node (ref "D223") (pin "1") (pinfunction "A_1") (pintype "passive"))
      (node (ref "S223") (pin "1") (pinfunction "1_1") (pintype "passive"))
    )
    (net (code "42") (name "Net-(D224-A)") (class "Default")
      (node (ref "D224") (pin "1") (pinfunction "A_1") (pintype "passive"))
      (node (ref "S224") (pin "1") (pinfunction "1_1") (pintype "passive"))
    )
    (net (code "43") (name "Net-(D225-A)") (class "Default")
      (node (ref "D225") (pin "1") (pinfunction "A_1") (pintype "passive"))
      (node (ref "S225") (pin "1") (pinfunction "1_1") (pintype "passive"))
    )
    (net (code "44") (name "Net-(D226-A)") (class "Default")
      (node (ref "D226") (pin "1") (pinfunction "A_1") (pintype "passive"))
      (node (ref "S226") (pin "1") (pinfunction "1_1") (pintype "passive"))
    )
    (net (code "45") (name "Net-(D227-A)") (class "Default")
      (node (ref "D227") (pin "1") (pinfunction "A_1") (pintype "passive"))
      (node (ref "S227") (pin "1") (pinfunction "1_1") (pintype "passive"))
    )
    (net (code "46") (name "Net-(D228-A)") (class "Default")
      (node (ref "D228") (pin "1") (pinfunction "A_1") (pintype "passive"))
      (node (ref "S228") (pin "2") (pinfunction "2_2") (pintype "passive"))
    )
    (net (code "47") (name "Net-(D229-A)") (class "Default")
      (node (ref "D229") (pin "1") (pinfunction "A_1") (pintype "passive"))
      (node (ref "S229") (pin "1") (pinfunction "1_1") (pintype "passive"))
    )
    (net (code "48") (name "Net-(D230-A)") (class "Default")
      (node (ref "D230") (pin "1") (pinfunction "A_1") (pintype "passive"))
      (node (ref "S230") (pin "1") (pinfunction "1_1") (pintype "passive"))
    )
    (net (code "49") (name "Net-(D231-A)") (class "Default")
      (node (ref "D231") (pin "1") (pinfunction "A_1") (pintype "passive"))
      (node (ref "S231") (pin "1") (pinfunction "1_1") (pintype "passive"))
    )
    (net (code "50") (name "Net-(D232-A)") (class "Default")
      (node (ref "D232") (pin "1") (pinfunction "A_1") (pintype "passive"))
      (node (ref "S232") (pin "1") (pinfunction "1_1") (pintype "passive"))
    )
    (net (code "51") (name "Net-(D233-A)") (class "Default")
      (node (ref "D233") (pin "1") (pinfunction "A_1") (pintype "passive"))
      (node (ref "S233") (pin "1") (pinfunction "1_1") (pintype "passive"))
    )
    (net (code "52") (name "Net-(D234-A)") (class "Default")
      (node (ref "D234") (pin "1") (pinfunction "A_1") (pintype "passive"))
      (node (ref "S234") (pin "1") (pinfunction "1_1") (pintype "passive"))
    )
    (net (code "53") (name "Net-(D235-A)") (class "Default")
      (node (ref "D235") (pin "1") (pinfunction "A_1") (pintype "passive"))
      (node (ref "S235") (pin "1") (pinfunction "1_1") (pintype "passive"))
    )
    (net (code "54") (name "Net-(D236-A)") (class "Default")
      (node (ref "D236") (pin "1") (pinfunction "A_1") (pintype "passive"))
      (node (ref "S236") (pin "1") (pinfunction "1_1") (pintype "passive"))
    )
    (net (code "55") (name "Net-(D237-A)") (class "Default")
      (node (ref "D237") (pin "1") (pinfunction "A_1") (pintype "passive"))
      (node (ref "S237") (pin "1") (pinfunction "1_1") (pintype "passive"))
    )
    (net (code "56") (name "Net-(D238-A)") (class "Default")
      (node (ref "D238") (pin "1") (pinfunction "A_1") (pintype "passive"))
      (node (ref "S238") (pin "1") (pinfunction "1_1") (pintype "passive"))
    )
    (net (code "57") (name "Net-(D239-A)") (class "Default")
      (node (ref "D239") (pin "1") (pinfunction "A_1") (pintype "passive"))
      (node (ref "S239") (pin "1") (pinfunction "1_1") (pintype "passive"))
    )
    (net (code "58") (name "Net-(D240-A)") (class "Default")
      (node (ref "D240") (pin "1") (pinfunction "A_1") (pintype "passive"))
      (node (ref "S240") (pin "1") (pinfunction "1_1") (pintype "passive"))
    )
    (net (code "59") (name "Net-(D241-A)") (class "Default")
      (node (ref "D241") (pin "1") (pinfunction "A_1") (pintype "passive"))
      (node (ref "S241") (pin "1") (pinfunction "1_1") (pintype "passive"))
    )
    (net (code "60") (name "Net-(D242-A)") (class "Default")
      (node (ref "D242") (pin "1") (pinfunction "A_1") (pintype "passive"))
      (node (ref "S242") (pin "1") (pinfunction "1_1") (pintype "passive"))
    )
    (net (code "61") (name "Net-(D243-A)") (class "Default")
      (node (ref "D243") (pin "1") (pinfunction "A_1") (pintype "passive"))
      (node (ref "S243") (pin "1") (pinfunction "1_1") (pintype "passive"))
    )
    (net (code "62") (name "Net-(D244-A)") (class "Default")
      (node (ref "D244") (pin "1") (pinfunction "A_1") (pintype "passive"))
      (node (ref "S244") (pin "1") (pinfunction "1_1") (pintype "passive"))
    )
    (net (code "63") (name "Net-(D245-A)") (class "Default")
      (node (ref "D245") (pin "1") (pinfunction "A_1") (pintype "passive"))
      (node (ref "S245") (pin "1") (pinfunction "1_1") (pintype "passive"))
    )
    (net (code "64") (name "Net-(D246-A)") (class "Default")
      (node (ref "D246") (pin "1") (pinfunction "A_1") (pintype "passive"))
      (node (ref "S246") (pin "1") (pinfunction "1_1") (pintype "passive"))
    )
    (net (code "65") (name "Net-(D247-A)") (class "Default")
      (node (ref "D247") (pin "1") (pinfunction "A_1") (pintype "passive"))
      (node (ref "S247") (pin "1") (pinfunction "1_1") (pintype "passive"))
    )
    (net (code "66") (name "Net-(D248-A)") (class "Default")
      (node (ref "D248") (pin "1") (pinfunction "A_1") (pintype "passive"))
      (node (ref "S248") (pin "1") (pinfunction "1_1") (pintype "passive"))
    )
    (net (code "67") (name "Net-(D249-A)") (class "Default")
      (node (ref "D249") (pin "1") (pinfunction "A_1") (pintype "passive"))
      (node (ref "S249") (pin "1") (pinfunction "1_1") (pintype "passive"))
    )
    (net (code "68") (name "Net-(D250-A)") (class "Default")
      (node (ref "D250") (pin "1") (pinfunction "A_1") (pintype "passive"))
      (node (ref "S250") (pin "1") (pinfunction "1_1") (pintype "passive"))
    )
    (net (code "69") (name "Net-(D251-A)") (class "Default")
      (node (ref "D251") (pin "1") (pinfunction "A_1") (pintype "passive"))
      (node (ref "S251") (pin "1") (pinfunction "1_1") (pintype "passive"))
    )
    (net (code "70") (name "Net-(D252-A)") (class "Default")
      (node (ref "D252") (pin "1") (pinfunction "A_1") (pintype "passive"))
      (node (ref "S252") (pin "1") (pinfunction "1_1") (pintype "passive"))
    )
    (net (code "71") (name "Net-(D253-A)") (class "Default")
      (node (ref "D253") (pin "1") (pinfunction "A_1") (pintype "passive"))
      (node (ref "S253") (pin "1") (pinfunction "1_1") (pintype "passive"))
    )
    (net (code "72") (name "Net-(D254-A)") (class "Default")
      (node (ref "D254") (pin "1") (pinfunction "A_1") (pintype "passive"))
      (node (ref "S254") (pin "1") (pinfunction "1_1") (pintype "passive"))
    )
    (net (code "73") (name "Net-(D255-A)") (class "Default")
      (node (ref "D255") (pin "1") (pinfunction "A_1") (pintype "passive"))
      (node (ref "S255") (pin "1") (pinfunction "1_1") (pintype "passive"))
    )
    (net (code "74") (name "Net-(D256-A)") (class "Default")
      (node (ref "D256") (pin "1") (pinfunction "A_1") (pintype "passive"))
      (node (ref "S256") (pin "1") (pinfunction "1_1") (pintype "passive"))
    )
    (net (code "75") (name "Net-(D257-A)") (class "Default")
      (node (ref "D257") (pin "1") (pinfunction "A_1") (pintype "passive"))
      (node (ref "S257") (pin "1") (pinfunction "1_1") (pintype "passive"))
    )
    (net (code "76") (name "Net-(D258-A)") (class "Default")
      (node (ref "D258") (pin "1") (pinfunction "A_1") (pintype "passive"))
      (node (ref "S258") (pin "1") (pinfunction "1_1") (pintype "passive"))
    )
    (net (code "77") (name "Net-(D259-A)") (class "Default")
      (node (ref "D259") (pin "1") (pinfunction "A_1") (pintype "passive"))
      (node (ref "S259") (pin "1") (pinfunction "1_1") (pintype "passive"))
    )
    (net (code "78") (name "Net-(D260-A)") (class "Default")
      (node (ref "D260") (pin "1") (pinfunction "A_1") (pintype "passive"))
      (node (ref "S260") (pin "1") (pinfunction "1_1") (pintype "passive"))
    )
    (net (code "79") (name "Net-(D261-A)") (class "Default")
      (node (ref "D261") (pin "1") (pinfunction "A_1") (pintype "passive"))
      (node (ref "S261") (pin "2") (pinfunction "2_2") (pintype "passive"))
    )
    (net (code "80") (name "Net-(D262-A)") (class "Default")
      (node (ref "D262") (pin "1") (pinfunction "A_1") (pintype "passive"))
      (node (ref "S262") (pin "1") (pinfunction "1_1") (pintype "passive"))
    )
    (net (code "81") (name "Net-(D263-A)") (class "Default")
      (node (ref "D263") (pin "1") (pinfunction "A_1") (pintype "passive"))
      (node (ref "S263") (pin "1") (pinfunction "1_1") (pintype "passive"))
    )
    (net (code "82") (name "Net-(D264-A)") (class "Default")
      (node (ref "D264") (pin "1") (pinfunction "A_1") (pintype "passive"))
      (node (ref "S264") (pin "2") (pinfunction "2_2") (pintype "passive"))
    )
    (net (code "83") (name "Net-(D265-A)") (class "Default")
      (node (ref "D265") (pin "1") (pinfunction "A_1") (pintype "passive"))
      (node (ref "S265") (pin "1") (pinfunction "1_1") (pintype "passive"))
    )
    (net (code "84") (name "Net-(D266-A)") (class "Default")
      (node (ref "D266") (pin "1") (pinfunction "A_1") (pintype "passive"))
      (node (ref "S266") (pin "1") (pinfunction "1_1") (pintype "passive"))
    )
    (net (code "85") (name "Net-(D267-A)") (class "Default")
      (node (ref "D267") (pin "1") (pinfunction "A_1") (pintype "passive"))
      (node (ref "S267") (pin "1") (pinfunction "1_1") (pintype "passive"))
    )
  )
)
